# PWR.net
KiCad netlist of a schematic drawn in EAGLE
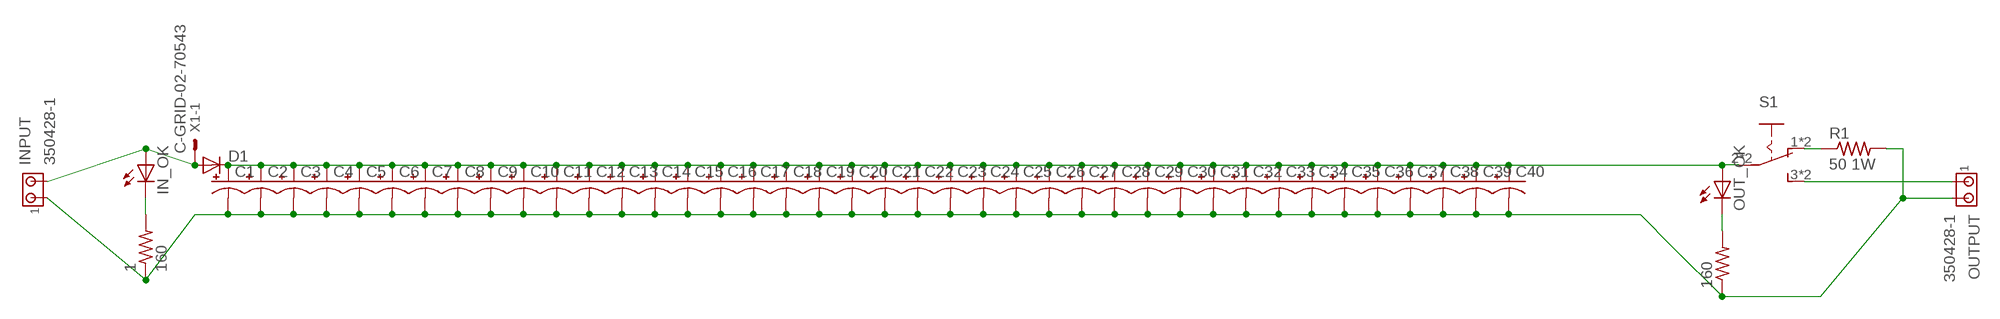
[diagram p0: schematic, sheet 1]

(export (version "E")
  (design (tool "Eeschema 10.0.6"))
  (components
    (comp (ref "1")
      (value "160")
      (footprint "eagle-import:R1206")
      (libsource (lib "eagle-import") (part "R-US_R1206"))
    )
    (comp (ref "160")
      (value "R-US_R1206")
      (footprint "eagle-import:R1206")
      (libsource (lib "eagle-import") (part "R-US_R1206"))
    )
    (comp (ref "C1")
      (value "CPOL-USE5-10.5")
      (footprint "eagle-import:E5-10,5")
      (libsource (lib "eagle-import") (part "CPOL-USE5-10.5"))
    )
    (comp (ref "C2")
      (value "CPOL-USE5-10.5")
      (footprint "eagle-import:E5-10,5")
      (libsource (lib "eagle-import") (part "CPOL-USE5-10.5"))
    )
    (comp (ref "C3")
      (value "CPOL-USE5-10.5")
      (footprint "eagle-import:E5-10,5")
      (libsource (lib "eagle-import") (part "CPOL-USE5-10.5"))
    )
    (comp (ref "C4")
      (value "CPOL-USE5-10.5")
      (footprint "eagle-import:E5-10,5")
      (libsource (lib "eagle-import") (part "CPOL-USE5-10.5"))
    )
    (comp (ref "C5")
      (value "CPOL-USE5-10.5")
      (footprint "eagle-import:E5-10,5")
      (libsource (lib "eagle-import") (part "CPOL-USE5-10.5"))
    )
    (comp (ref "C6")
      (value "CPOL-USE5-10.5")
      (footprint "eagle-import:E5-10,5")
      (libsource (lib "eagle-import") (part "CPOL-USE5-10.5"))
    )
    (comp (ref "C7")
      (value "CPOL-USE5-10.5")
      (footprint "eagle-import:E5-10,5")
      (libsource (lib "eagle-import") (part "CPOL-USE5-10.5"))
    )
    (comp (ref "C8")
      (value "CPOL-USE5-10.5")
      (footprint "eagle-import:E5-10,5")
      (libsource (lib "eagle-import") (part "CPOL-USE5-10.5"))
    )
    (comp (ref "C9")
      (value "CPOL-USE5-10.5")
      (footprint "eagle-import:E5-10,5")
      (libsource (lib "eagle-import") (part "CPOL-USE5-10.5"))
    )
    (comp (ref "C10")
      (value "CPOL-USE5-10.5")
      (footprint "eagle-import:E5-10,5")
      (libsource (lib "eagle-import") (part "CPOL-USE5-10.5"))
    )
    (comp (ref "C11")
      (value "CPOL-USE5-10.5")
      (footprint "eagle-import:E5-10,5")
      (libsource (lib "eagle-import") (part "CPOL-USE5-10.5"))
    )
    (comp (ref "C12")
      (value "CPOL-USE5-10.5")
      (footprint "eagle-import:E5-10,5")
      (libsource (lib "eagle-import") (part "CPOL-USE5-10.5"))
    )
    (comp (ref "C13")
      (value "CPOL-USE5-10.5")
      (footprint "eagle-import:E5-10,5")
      (libsource (lib "eagle-import") (part "CPOL-USE5-10.5"))
    )
    (comp (ref "C14")
      (value "CPOL-USE5-10.5")
      (footprint "eagle-import:E5-10,5")
      (libsource (lib "eagle-import") (part "CPOL-USE5-10.5"))
    )
    (comp (ref "C15")
      (value "CPOL-USE5-10.5")
      (footprint "eagle-import:E5-10,5")
      (libsource (lib "eagle-import") (part "CPOL-USE5-10.5"))
    )
    (comp (ref "C16")
      (value "CPOL-USE5-10.5")
      (footprint "eagle-import:E5-10,5")
      (libsource (lib "eagle-import") (part "CPOL-USE5-10.5"))
    )
    (comp (ref "C17")
      (value "CPOL-USE5-10.5")
      (footprint "eagle-import:E5-10,5")
      (libsource (lib "eagle-import") (part "CPOL-USE5-10.5"))
    )
    (comp (ref "C18")
      (value "CPOL-USE5-10.5")
      (footprint "eagle-import:E5-10,5")
      (libsource (lib "eagle-import") (part "CPOL-USE5-10.5"))
    )
    (comp (ref "C19")
      (value "CPOL-USE5-10.5")
      (footprint "eagle-import:E5-10,5")
      (libsource (lib "eagle-import") (part "CPOL-USE5-10.5"))
    )
    (comp (ref "C20")
      (value "CPOL-USE5-10.5")
      (footprint "eagle-import:E5-10,5")
      (libsource (lib "eagle-import") (part "CPOL-USE5-10.5"))
    )
    (comp (ref "C21")
      (value "CPOL-USE5-10.5")
      (footprint "eagle-import:E5-10,5")
      (libsource (lib "eagle-import") (part "CPOL-USE5-10.5"))
    )
    (comp (ref "C22")
      (value "CPOL-USE5-10.5")
      (footprint "eagle-import:E5-10,5")
      (libsource (lib "eagle-import") (part "CPOL-USE5-10.5"))
    )
    (comp (ref "C23")
      (value "CPOL-USE5-10.5")
      (footprint "eagle-import:E5-10,5")
      (libsource (lib "eagle-import") (part "CPOL-USE5-10.5"))
    )
    (comp (ref "C24")
      (value "CPOL-USE5-10.5")
      (footprint "eagle-import:E5-10,5")
      (libsource (lib "eagle-import") (part "CPOL-USE5-10.5"))
    )
    (comp (ref "C25")
      (value "CPOL-USE5-10.5")
      (footprint "eagle-import:E5-10,5")
      (libsource (lib "eagle-import") (part "CPOL-USE5-10.5"))
    )
    (comp (ref "C26")
      (value "CPOL-USE5-10.5")
      (footprint "eagle-import:E5-10,5")
      (libsource (lib "eagle-import") (part "CPOL-USE5-10.5"))
    )
    (comp (ref "C27")
      (value "CPOL-USE5-10.5")
      (footprint "eagle-import:E5-10,5")
      (libsource (lib "eagle-import") (part "CPOL-USE5-10.5"))
    )
    (comp (ref "C28")
      (value "CPOL-USE5-10.5")
      (footprint "eagle-import:E5-10,5")
      (libsource (lib "eagle-import") (part "CPOL-USE5-10.5"))
    )
    (comp (ref "C29")
      (value "CPOL-USE5-10.5")
      (footprint "eagle-import:E5-10,5")
      (libsource (lib "eagle-import") (part "CPOL-USE5-10.5"))
    )
    (comp (ref "C30")
      (value "CPOL-USE5-10.5")
      (footprint "eagle-import:E5-10,5")
      (libsource (lib "eagle-import") (part "CPOL-USE5-10.5"))
    )
    (comp (ref "C31")
      (value "CPOL-USE5-10.5")
      (footprint "eagle-import:E5-10,5")
      (libsource (lib "eagle-import") (part "CPOL-USE5-10.5"))
    )
    (comp (ref "C32")
      (value "CPOL-USE5-10.5")
      (footprint "eagle-import:E5-10,5")
      (libsource (lib "eagle-import") (part "CPOL-USE5-10.5"))
    )
    (comp (ref "C33")
      (value "CPOL-USE5-10.5")
      (footprint "eagle-import:E5-10,5")
      (libsource (lib "eagle-import") (part "CPOL-USE5-10.5"))
    )
    (comp (ref "C34")
      (value "CPOL-USE5-10.5")
      (footprint "eagle-import:E5-10,5")
      (libsource (lib "eagle-import") (part "CPOL-USE5-10.5"))
    )
    (comp (ref "C35")
      (value "CPOL-USE5-10.5")
      (footprint "eagle-import:E5-10,5")
      (libsource (lib "eagle-import") (part "CPOL-USE5-10.5"))
    )
    (comp (ref "C36")
      (value "CPOL-USE5-10.5")
      (footprint "eagle-import:E5-10,5")
      (libsource (lib "eagle-import") (part "CPOL-USE5-10.5"))
    )
    (comp (ref "C37")
      (value "CPOL-USE5-10.5")
      (footprint "eagle-import:E5-10,5")
      (libsource (lib "eagle-import") (part "CPOL-USE5-10.5"))
    )
    (comp (ref "C38")
      (value "CPOL-USE5-10.5")
      (footprint "eagle-import:E5-10,5")
      (libsource (lib "eagle-import") (part "CPOL-USE5-10.5"))
    )
    (comp (ref "C39")
      (value "CPOL-USE5-10.5")
      (footprint "eagle-import:E5-10,5")
      (libsource (lib "eagle-import") (part "CPOL-USE5-10.5"))
    )
    (comp (ref "C40")
      (value "CPOL-USE5-10.5")
      (footprint "eagle-import:E5-10,5")
      (libsource (lib "eagle-import") (part "CPOL-USE5-10.5"))
    )
    (comp (ref "D1")
      (value "DIODE-SOD123")
      (footprint "eagle-import:SOD123")
      (libsource (lib "eagle-import") (part "DIODE-SOD123"))
    )
    (comp (ref "INPUT")
      (value "350428-1")
      (footprint "eagle-import:350428-1")
      (libsource (lib "eagle-import") (part "350428-1"))
    )
    (comp (ref "IN_OK")
      (value "LEDCHIPLED_1206")
      (footprint "eagle-import:CHIPLED_1206")
      (libsource (lib "eagle-import") (part "LEDCHIPLED_1206"))
    )
    (comp (ref "OUTPUT")
      (value "350428-1")
      (footprint "eagle-import:350428-1")
      (libsource (lib "eagle-import") (part "350428-1"))
    )
    (comp (ref "OUT_OK")
      (value "LEDCHIPLED_1206")
      (footprint "eagle-import:CHIPLED_1206")
      (libsource (lib "eagle-import") (part "LEDCHIPLED_1206"))
    )
    (comp (ref "R1")
      (value "50 1W")
      (footprint "eagle-import:WSC2515")
      (libsource (lib "eagle-import") (part "R-US_WSC2515"))
    )
    (comp (ref "S1")
      (value "M251")
      (footprint "eagle-import:SLIDE_SWITCH")
      (libsource (lib "eagle-import") (part "M251"))
    )
    (comp (ref "X1")
      (value "C-GRID-02-70543")
      (footprint "eagle-import:70543-02")
      (libsource (lib "eagle-import") (part "C-GRID-02-70543"))
    )
  )
  (nets
    (net (code "1") (name "Net-(1-Pad1)") (class "Default")
      (node (ref "1") (pin "1") (pinfunction "1_1") (pintype "passive"))
      (node (ref "160") (pin "1") (pinfunction "1_1") (pintype "passive"))
      (node (ref "C1") (pin "-") (pinfunction "-_-") (pintype "passive"))
      (node (ref "C10") (pin "-") (pinfunction "-_-") (pintype "passive"))
      (node (ref "C11") (pin "-") (pinfunction "-_-") (pintype "passive"))
      (node (ref "C12") (pin "-") (pinfunction "-_-") (pintype "passive"))
      (node (ref "C13") (pin "-") (pinfunction "-_-") (pintype "passive"))
      (node (ref "C14") (pin "-") (pinfunction "-_-") (pintype "passive"))
      (node (ref "C15") (pin "-") (pinfunction "-_-") (pintype "passive"))
      (node (ref "C16") (pin "-") (pinfunction "-_-") (pintype "passive"))
      (node (ref "C17") (pin "-") (pinfunction "-_-") (pintype "passive"))
      (node (ref "C18") (pin "-") (pinfunction "-_-") (pintype "passive"))
      (node (ref "C19") (pin "-") (pinfunction "-_-") (pintype "passive"))
      (node (ref "C2") (pin "-") (pinfunction "-_-") (pintype "passive"))
      (node (ref "C20") (pin "-") (pinfunction "-_-") (pintype "passive"))
      (node (ref "C21") (pin "-") (pinfunction "-_-") (pintype "passive"))
      (node (ref "C22") (pin "-") (pinfunction "-_-") (pintype "passive"))
      (node (ref "C23") (pin "-") (pinfunction "-_-") (pintype "passive"))
      (node (ref "C24") (pin "-") (pinfunction "-_-") (pintype "passive"))
      (node (ref "C25") (pin "-") (pinfunction "-_-") (pintype "passive"))
      (node (ref "C26") (pin "-") (pinfunction "-_-") (pintype "passive"))
      (node (ref "C27") (pin "-") (pinfunction "-_-") (pintype "passive"))
      (node (ref "C28") (pin "-") (pinfunction "-_-") (pintype "passive"))
      (node (ref "C29") (pin "-") (pinfunction "-_-") (pintype "passive"))
      (node (ref "C3") (pin "-") (pinfunction "-_-") (pintype "passive"))
      (node (ref "C30") (pin "-") (pinfunction "-_-") (pintype "passive"))
      (node (ref "C31") (pin "-") (pinfunction "-_-") (pintype "passive"))
      (node (ref "C32") (pin "-") (pinfunction "-_-") (pintype "passive"))
      (node (ref "C33") (pin "-") (pinfunction "-_-") (pintype "passive"))
      (node (ref "C34") (pin "-") (pinfunction "-_-") (pintype "passive"))
      (node (ref "C35") (pin "-") (pinfunction "-_-") (pintype "passive"))
      (node (ref "C36") (pin "-") (pinfunction "-_-") (pintype "passive"))
      (node (ref "C37") (pin "-") (pinfunction "-_-") (pintype "passive"))
      (node (ref "C38") (pin "-") (pinfunction "-_-") (pintype "passive"))
      (node (ref "C39") (pin "-") (pinfunction "-_-") (pintype "passive"))
      (node (ref "C4") (pin "-") (pinfunction "-_-") (pintype "passive"))
      (node (ref "C40") (pin "-") (pinfunction "-_-") (pintype "passive"))
      (node (ref "C5") (pin "-") (pinfunction "-_-") (pintype "passive"))
      (node (ref "C6") (pin "-") (pinfunction "-_-") (pintype "passive"))
      (node (ref "C7") (pin "-") (pinfunction "-_-") (pintype "passive"))
      (node (ref "C8") (pin "-") (pinfunction "-_-") (pintype "passive"))
      (node (ref "C9") (pin "-") (pinfunction "-_-") (pintype "passive"))
      (node (ref "INPUT") (pin "1") (pinfunction "1_1") (pintype "passive"))
      (node (ref "OUTPUT") (pin "2") (pinfunction "2_2") (pintype "passive"))
      (node (ref "R1") (pin "2") (pinfunction "2_2") (pintype "passive"))
    )
    (net (code "2") (name "Net-(1-Pad2)") (class "Default")
      (node (ref "1") (pin "2") (pinfunction "2_2") (pintype "passive"))
      (node (ref "IN_OK") (pin "C") (pinfunction "C_C") (pintype "passive"))
    )
    (net (code "3") (name "Net-(160-Pad2)") (class "Default")
      (node (ref "160") (pin "2") (pinfunction "2_2") (pintype "passive"))
      (node (ref "OUT_OK") (pin "C") (pinfunction "C_C") (pintype "passive"))
    )
    (net (code "4") (name "Net-(C1-Pad+)") (class "Default")
      (node (ref "C1") (pin "+") (pinfunction "+_+") (pintype "passive"))
      (node (ref "C10") (pin "+") (pinfunction "+_+") (pintype "passive"))
      (node (ref "C11") (pin "+") (pinfunction "+_+") (pintype "passive"))
      (node (ref "C12") (pin "+") (pinfunction "+_+") (pintype "passive"))
      (node (ref "C13") (pin "+") (pinfunction "+_+") (pintype "passive"))
      (node (ref "C14") (pin "+") (pinfunction "+_+") (pintype "passive"))
      (node (ref "C15") (pin "+") (pinfunction "+_+") (pintype "passive"))
      (node (ref "C16") (pin "+") (pinfunction "+_+") (pintype "passive"))
      (node (ref "C17") (pin "+") (pinfunction "+_+") (pintype "passive"))
      (node (ref "C18") (pin "+") (pinfunction "+_+") (pintype "passive"))
      (node (ref "C19") (pin "+") (pinfunction "+_+") (pintype "passive"))
      (node (ref "C2") (pin "+") (pinfunction "+_+") (pintype "passive"))
      (node (ref "C20") (pin "+") (pinfunction "+_+") (pintype "passive"))
      (node (ref "C21") (pin "+") (pinfunction "+_+") (pintype "passive"))
      (node (ref "C22") (pin "+") (pinfunction "+_+") (pintype "passive"))
      (node (ref "C23") (pin "+") (pinfunction "+_+") (pintype "passive"))
      (node (ref "C24") (pin "+") (pinfunction "+_+") (pintype "passive"))
      (node (ref "C25") (pin "+") (pinfunction "+_+") (pintype "passive"))
      (node (ref "C26") (pin "+") (pinfunction "+_+") (pintype "passive"))
      (node (ref "C27") (pin "+") (pinfunction "+_+") (pintype "passive"))
      (node (ref "C28") (pin "+") (pinfunction "+_+") (pintype "passive"))
      (node (ref "C29") (pin "+") (pinfunction "+_+") (pintype "passive"))
      (node (ref "C3") (pin "+") (pinfunction "+_+") (pintype "passive"))
      (node (ref "C30") (pin "+") (pinfunction "+_+") (pintype "passive"))
      (node (ref "C31") (pin "+") (pinfunction "+_+") (pintype "passive"))
      (node (ref "C32") (pin "+") (pinfunction "+_+") (pintype "passive"))
      (node (ref "C33") (pin "+") (pinfunction "+_+") (pintype "passive"))
      (node (ref "C34") (pin "+") (pinfunction "+_+") (pintype "passive"))
      (node (ref "C35") (pin "+") (pinfunction "+_+") (pintype "passive"))
      (node (ref "C36") (pin "+") (pinfunction "+_+") (pintype "passive"))
      (node (ref "C37") (pin "+") (pinfunction "+_+") (pintype "passive"))
      (node (ref "C38") (pin "+") (pinfunction "+_+") (pintype "passive"))
      (node (ref "C39") (pin "+") (pinfunction "+_+") (pintype "passive"))
      (node (ref "C4") (pin "+") (pinfunction "+_+") (pintype "passive"))
      (node (ref "C40") (pin "+") (pinfunction "+_+") (pintype "passive"))
      (node (ref "C5") (pin "+") (pinfunction "+_+") (pintype "passive"))
      (node (ref "C6") (pin "+") (pinfunction "+_+") (pintype "passive"))
      (node (ref "C7") (pin "+") (pinfunction "+_+") (pintype "passive"))
      (node (ref "C8") (pin "+") (pinfunction "+_+") (pintype "passive"))
      (node (ref "C9") (pin "+") (pinfunction "+_+") (pintype "passive"))
      (node (ref "D1") (pin "C") (pinfunction "C_C") (pintype "passive"))
      (node (ref "OUT_OK") (pin "A") (pinfunction "A_A") (pintype "passive"))
      (node (ref "S1") (pin "2") (pinfunction "P_2") (pintype "passive"))
      (node (ref "S1") (pin "5") (pinfunction "P_5") (pintype "passive"))
    )
    (net (code "5") (name "Net-(OUTPUT-Pad1)") (class "Default")
      (node (ref "OUTPUT") (pin "1") (pinfunction "1_1") (pintype "passive"))
      (node (ref "S1") (pin "3") (pinfunction "S_3") (pintype "passive"))
      (node (ref "S1") (pin "4") (pinfunction "S_4") (pintype "passive"))
    )
    (net (code "6") (name "Net-(R1-Pad1)") (class "Default")
      (node (ref "R1") (pin "1") (pinfunction "1_1") (pintype "passive"))
      (node (ref "S1") (pin "1") (pinfunction "O_1") (pintype "passive"))
      (node (ref "S1") (pin "6") (pinfunction "O_6") (pintype "passive"))
    )
    (net (code "7") (name "Net-(X1A-S)") (class "Default")
      (node (ref "D1") (pin "A") (pinfunction "A_A") (pintype "passive"))
      (node (ref "INPUT") (pin "2") (pinfunction "2_2") (pintype "passive"))
      (node (ref "IN_OK") (pin "A") (pinfunction "A_A") (pintype "passive"))
      (node (ref "X1") (pin "1") (pinfunction "S_1") (pintype "passive"))
    )
  )
)
